# PogoBattPack.net
KiCad netlist of a schematic drawn in Altium Designer
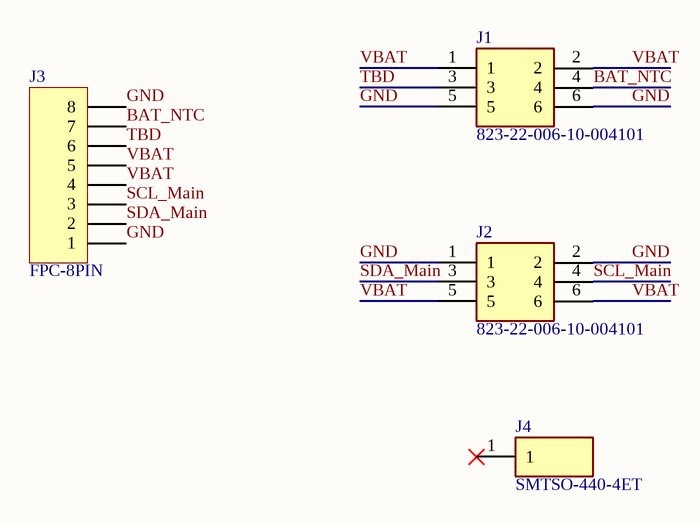
[diagram p0: PogoBattPack.SchDoc]

(export (version "E")
  (design (tool "Eeschema 10.0.6"))
  (components
    (comp (ref "J1")
      (value "823-22-006-10-004101")
      (footprint "HDRV6W43P254_2X3_762X508X599P")
      (description "Connector")
      (fields (field (name "MOUSER PART NUMBER") "575-8232200610004101"))
      (libsource (lib "823-22-006-10-004101 Pogo") (part "823-22-006-10-004101"))
    )
    (comp (ref "J2")
      (value "823-22-006-10-004101")
      (footprint "HDRV6W43P254_2X3_762X508X599P")
      (description "Connector")
      (fields (field (name "MOUSER PART NUMBER") "575-8232200610004101"))
      (libsource (lib "823-22-006-10-004101 Pogo") (part "823-22-006-10-004101"))
    )
    (comp (ref "J3")
      (value "FPC-8PIN")
      (footprint "FPC-PCB-8PIN")
      (description "Header, 8-Pin")
      (fields (field (name "PUBLISHER") "Altium Limited"))
      (libsource (lib "Miscellaneous Connectors") (part "Header 8"))
    )
    (comp (ref "J4")
      (value "SMTSO-440-4ET")
      (footprint "SMTSO-440-4ET Conn:SMTSO-440-4ET")
      (description "Connector")
      (fields
        (field (name "MANUFACTURER_PART_NUMBER") "746600330R")
        (field (name "MOUSER PART NUMBER") "710-746600330R")
      )
      (libsource (lib "SMTSO-440-4ET Conn") (part "SMTSO-440-4ET"))
    )
  )
  (nets
    (net (code "1") (name "/BAT_NTC") (class "Default")
      (node (ref "J1") (pin "4") (pinfunction "4_4") (pintype "passive"))
      (node (ref "J3") (pin "7") (pinfunction "7_7") (pintype "passive"))
    )
    (net (code "2") (name "/GND") (class "Default")
      (node (ref "J1") (pin "5") (pinfunction "5_5") (pintype "passive"))
      (node (ref "J1") (pin "6") (pinfunction "6_6") (pintype "passive"))
      (node (ref "J2") (pin "1") (pinfunction "1_1") (pintype "passive"))
      (node (ref "J2") (pin "2") (pinfunction "2_2") (pintype "passive"))
      (node (ref "J3") (pin "1") (pinfunction "1_1") (pintype "passive"))
      (node (ref "J3") (pin "8") (pinfunction "8_8") (pintype "passive"))
    )
    (net (code "3") (name "/SCL_Main") (class "Default")
      (node (ref "J2") (pin "4") (pinfunction "4_4") (pintype "passive"))
      (node (ref "J3") (pin "3") (pinfunction "3_3") (pintype "passive"))
    )
    (net (code "4") (name "/SDA_Main") (class "Default")
      (node (ref "J2") (pin "3") (pinfunction "3_3") (pintype "passive"))
      (node (ref "J3") (pin "2") (pinfunction "2_2") (pintype "passive"))
    )
    (net (code "5") (name "/TBD") (class "Default")
      (node (ref "J1") (pin "3") (pinfunction "3_3") (pintype "passive"))
      (node (ref "J3") (pin "6") (pinfunction "6_6") (pintype "passive"))
    )
    (net (code "6") (name "/VBAT") (class "Default")
      (node (ref "J1") (pin "1") (pinfunction "1_1") (pintype "passive"))
      (node (ref "J1") (pin "2") (pinfunction "2_2") (pintype "passive"))
      (node (ref "J2") (pin "5") (pinfunction "5_5") (pintype "passive"))
      (node (ref "J2") (pin "6") (pinfunction "6_6") (pintype "passive"))
      (node (ref "J3") (pin "4") (pinfunction "4_4") (pintype "passive"))
      (node (ref "J3") (pin "5") (pinfunction "5_5") (pintype "passive"))
    )
    (net (code "7") (name "unconnected-(J4-Pad1)") (class "Default")
      (node (ref "J4") (pin "1") (pinfunction "1_1") (pintype "passive+no_connect"))
    )
  )
)
